# bat_v.net
KiCad netlist of a schematic drawn in Altium Designer
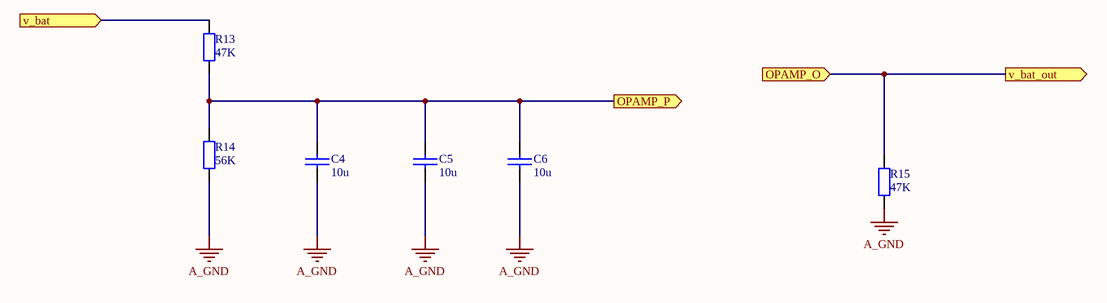
[diagram p0: bat_v.SchDoc]

(export (version "E")
  (design (tool "Eeschema 10.0.6"))
  (components
    (comp (ref "C4") (value "10u") (description "Capacitor") (libsource (lib "EceParts") (part "Cap")))
    (comp (ref "C5") (value "10u") (description "Capacitor") (libsource (lib "EceParts") (part "Cap")))
    (comp (ref "C6") (value "10u") (description "Capacitor") (libsource (lib "EceParts") (part "Cap")))
    (comp (ref "R13") (value "47K") (description "Resistor") (libsource (lib "EceParts") (part "Resistor")))
    (comp (ref "R14") (value "56K") (description "Resistor") (libsource (lib "EceParts") (part "Resistor")))
    (comp (ref "R15") (value "47K") (description "Resistor") (libsource (lib "EceParts") (part "Resistor")))
  )
  (nets
    (net (code "1") (name "/OPAMP_O") (class "Default")
      (node (ref "R15") (pin "2") (pinfunction "2_2") (pintype "passive"))
    )
    (net (code "2") (name "/OPAMP_P") (class "Default")
      (node (ref "C4") (pin "2") (pinfunction "2_2") (pintype "passive"))
      (node (ref "C5") (pin "2") (pinfunction "2_2") (pintype "passive"))
      (node (ref "C6") (pin "2") (pinfunction "2_2") (pintype "passive"))
      (node (ref "R13") (pin "1") (pinfunction "1_1") (pintype "passive"))
      (node (ref "R14") (pin "2") (pinfunction "2_2") (pintype "passive"))
    )
    (net (code "3") (name "/v_bat") (class "Default")
      (node (ref "R13") (pin "2") (pinfunction "2_2") (pintype "passive"))
    )
    (net (code "4") (name "A_GND") (class "Default")
      (node (ref "C4") (pin "1") (pinfunction "1_1") (pintype "passive"))
      (node (ref "C5") (pin "1") (pinfunction "1_1") (pintype "passive"))
      (node (ref "C6") (pin "1") (pinfunction "1_1") (pintype "passive"))
      (node (ref "R14") (pin "1") (pinfunction "1_1") (pintype "passive"))
      (node (ref "R15") (pin "1") (pinfunction "1_1") (pintype "passive"))
    )
  )
)
